# HVSupply.net
KiCad netlist of a schematic drawn in EAGLE
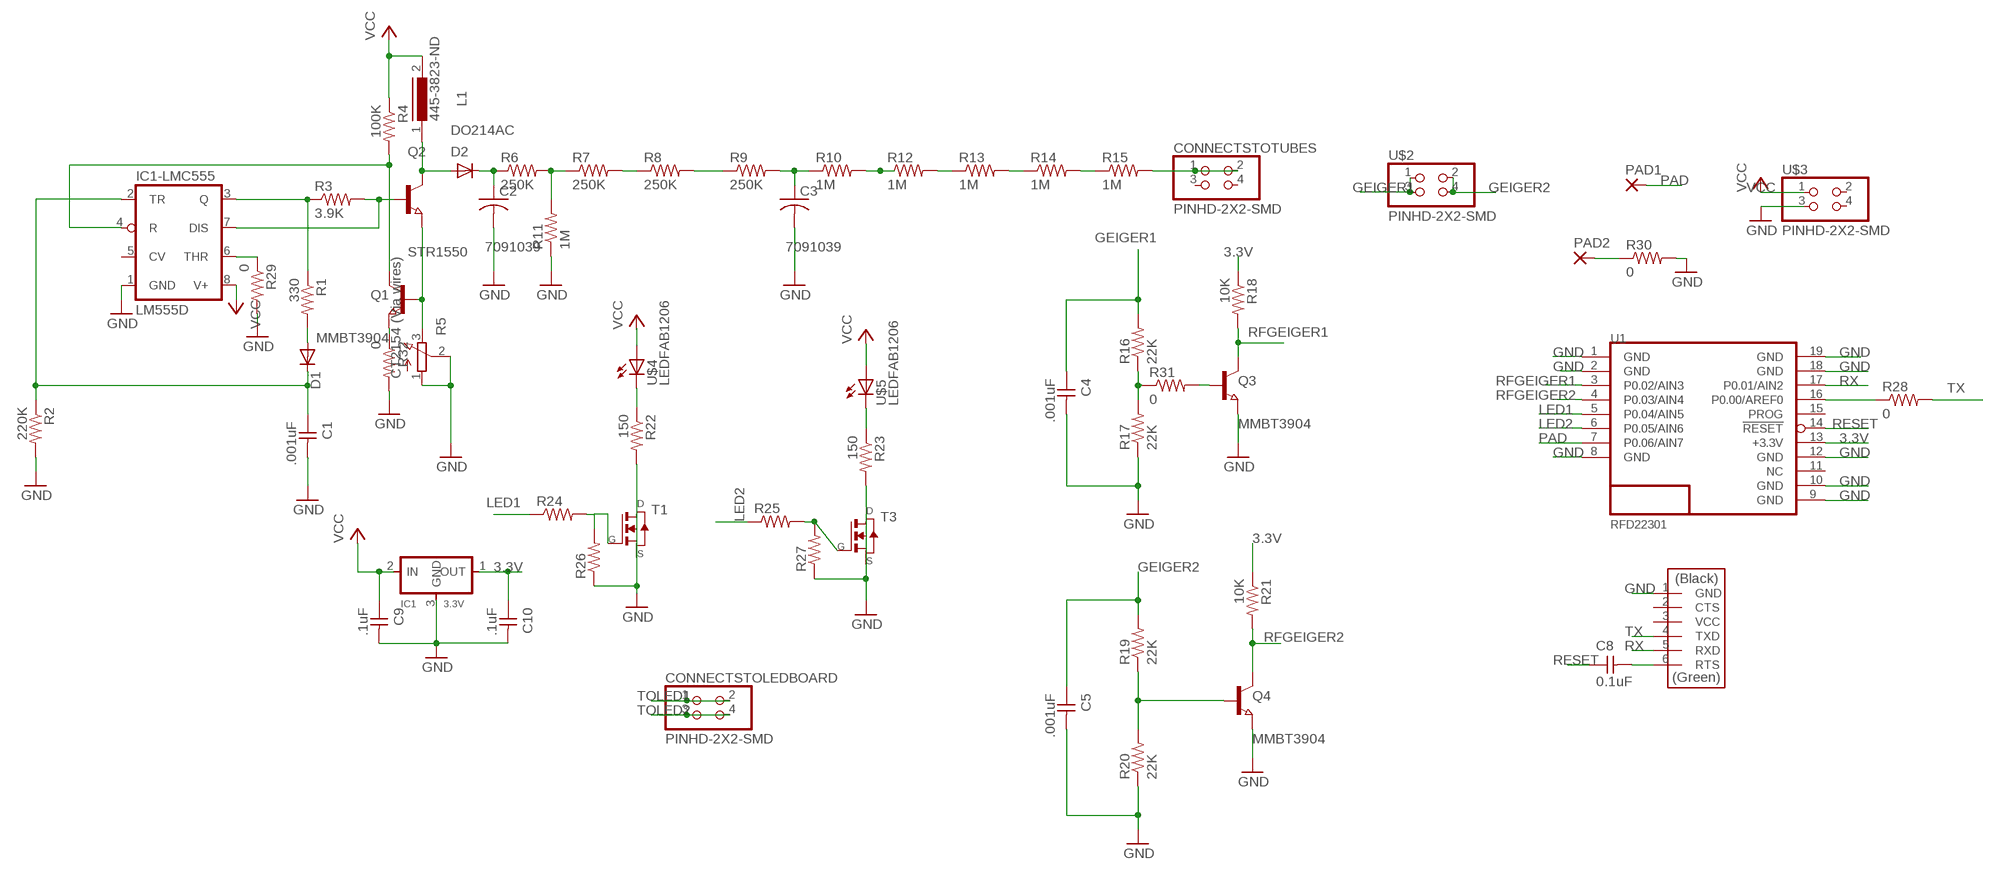
[diagram p0: schematic, sheet 1]

(export (version "E")
  (design (tool "Eeschema 10.0.6"))
  (components
    (comp (ref "C1")
      (value ".001uF")
      (footprint "eagle-import:C1206FAB")
      (libsource (lib "eagle-import") (part "CAP-UNPOLARIZEDFAB"))
    )
    (comp (ref "C2")
      (value "7091039")
      (footprint "eagle-import:C0603K")
      (libsource (lib "eagle-import") (part "C-USC0603K"))
    )
    (comp (ref "C3")
      (value "7091039")
      (footprint "eagle-import:C0603K")
      (libsource (lib "eagle-import") (part "C-USC0603K"))
    )
    (comp (ref "C4")
      (value ".001uF")
      (footprint "eagle-import:C1206FAB")
      (libsource (lib "eagle-import") (part "CAP-UNPOLARIZEDFAB"))
    )
    (comp (ref "C5")
      (value ".001uF")
      (footprint "eagle-import:C1206FAB")
      (libsource (lib "eagle-import") (part "CAP-UNPOLARIZEDFAB"))
    )
    (comp (ref "C8")
      (value "0.1uF")
      (footprint "eagle-import:C1206FAB")
      (libsource (lib "eagle-import") (part "CAP-UNPOLARIZEDFAB"))
    )
    (comp (ref "C9")
      (value ".1uF")
      (footprint "eagle-import:C1206FAB")
      (libsource (lib "eagle-import") (part "CAP-UNPOLARIZEDFAB"))
    )
    (comp (ref "C10")
      (value ".1uF")
      (footprint "eagle-import:C1206FAB")
      (libsource (lib "eagle-import") (part "CAP-UNPOLARIZEDFAB"))
    )
    (comp (ref "CONNECTSTOLEDBOARD")
      (value "PINHD-2X2-SMD")
      (footprint "eagle-import:2X02SMD")
      (libsource (lib "eagle-import") (part "PINHD-2X2-SMD"))
    )
    (comp (ref "CONNECTSTOTUBES")
      (value "PINHD-2X2-SMD")
      (footprint "eagle-import:2X02SMD")
      (libsource (lib "eagle-import") (part "PINHD-2X2-SMD"))
    )
    (comp (ref "D1")
      (value "DIODESOD123")
      (footprint "eagle-import:SOD123")
      (libsource (lib "eagle-import") (part "DIODESOD123"))
    )
    (comp (ref "D2")
      (value "DO214AC")
      (footprint "eagle-import:SMA-DO214AC")
      (libsource (lib "eagle-import") (part "GF1"))
    )
    (comp (ref "IC1")
      (value "3.3V")
      (footprint "eagle-import:SOT23")
      (libsource (lib "eagle-import") (part "REGULATORSOT23"))
    )
    (comp (ref "IC1-LMC555")
      (value "LM555D")
      (footprint "eagle-import:SO08")
      (libsource (lib "eagle-import") (part "555DLM"))
    )
    (comp (ref "L1")
      (value "445-3823-ND")
      (footprint "eagle-import:EMC9714")
      (libsource (lib "eagle-import") (part "EMC9714"))
    )
    (comp (ref "PAD1")
      (value "SMD5")
      (footprint "eagle-import:SMD2,54-5,08")
      (libsource (lib "eagle-import") (part "SMD5"))
    )
    (comp (ref "PAD2")
      (value "SMD5")
      (footprint "eagle-import:SMD2,54-5,08")
      (libsource (lib "eagle-import") (part "SMD5"))
    )
    (comp (ref "Q1")
      (value "MMBT3904")
      (footprint "eagle-import:SOT23")
      (libsource (lib "eagle-import") (part "NPN-TRANSISTOR_SOT23"))
    )
    (comp (ref "Q2")
      (value "STR1550")
      (footprint "eagle-import:SOT23")
      (libsource (lib "eagle-import") (part "NPN-TRANSISTOR_SOT23"))
    )
    (comp (ref "Q3")
      (value "MMBT3904")
      (footprint "eagle-import:SOT23")
      (libsource (lib "eagle-import") (part "NPN-TRANSISTOR_SOT23"))
    )
    (comp (ref "Q4")
      (value "MMBT3904")
      (footprint "eagle-import:SOT23")
      (libsource (lib "eagle-import") (part "NPN-TRANSISTOR_SOT23"))
    )
    (comp (ref "R1")
      (value "330")
      (footprint "eagle-import:R1206FAB")
      (libsource (lib "eagle-import") (part "RES-US1206FAB"))
    )
    (comp (ref "R2")
      (value "220K")
      (footprint "eagle-import:R1206FAB")
      (libsource (lib "eagle-import") (part "RES-US1206FAB"))
    )
    (comp (ref "R3")
      (value "3.9K")
      (footprint "eagle-import:R1206FAB")
      (libsource (lib "eagle-import") (part "RES-US1206FAB"))
    )
    (comp (ref "R4")
      (value "100K")
      (footprint "eagle-import:R1206FAB")
      (libsource (lib "eagle-import") (part "RES-US1206FAB"))
    )
    (comp (ref "R5")
      (value "CT2154 (Via wires)")
      (footprint "eagle-import:3RP_1610N")
      (libsource (lib "eagle-import") (part "3RP/1610N"))
    )
    (comp (ref "R6")
      (value "250K")
      (footprint "eagle-import:R1206FAB")
      (libsource (lib "eagle-import") (part "RES-US1206FAB"))
    )
    (comp (ref "R7")
      (value "250K")
      (footprint "eagle-import:R1206FAB")
      (libsource (lib "eagle-import") (part "RES-US1206FAB"))
    )
    (comp (ref "R8")
      (value "250K")
      (footprint "eagle-import:R1206FAB")
      (libsource (lib "eagle-import") (part "RES-US1206FAB"))
    )
    (comp (ref "R9")
      (value "250K")
      (footprint "eagle-import:R1206FAB")
      (libsource (lib "eagle-import") (part "RES-US1206FAB"))
    )
    (comp (ref "R10")
      (value "1M")
      (footprint "eagle-import:R1206FAB")
      (libsource (lib "eagle-import") (part "RES-US1206FAB"))
    )
    (comp (ref "R11")
      (value "1M")
      (footprint "eagle-import:R1206FAB")
      (libsource (lib "eagle-import") (part "RES-US1206FAB"))
    )
    (comp (ref "R12")
      (value "1M")
      (footprint "eagle-import:R1206FAB")
      (libsource (lib "eagle-import") (part "RES-US1206FAB"))
    )
    (comp (ref "R13")
      (value "1M")
      (footprint "eagle-import:R1206FAB")
      (libsource (lib "eagle-import") (part "RES-US1206FAB"))
    )
    (comp (ref "R14")
      (value "1M")
      (footprint "eagle-import:R1206FAB")
      (libsource (lib "eagle-import") (part "RES-US1206FAB"))
    )
    (comp (ref "R15")
      (value "1M")
      (footprint "eagle-import:R1206FAB")
      (libsource (lib "eagle-import") (part "RES-US1206FAB"))
    )
    (comp (ref "R16")
      (value "22K")
      (footprint "eagle-import:R1206FAB")
      (libsource (lib "eagle-import") (part "RES-US1206FAB"))
    )
    (comp (ref "R17")
      (value "22K")
      (footprint "eagle-import:R1206FAB")
      (libsource (lib "eagle-import") (part "RES-US1206FAB"))
    )
    (comp (ref "R18")
      (value "10K")
      (footprint "eagle-import:R1206FAB")
      (libsource (lib "eagle-import") (part "RES-US1206FAB"))
    )
    (comp (ref "R19")
      (value "22K")
      (footprint "eagle-import:R1206FAB")
      (libsource (lib "eagle-import") (part "RES-US1206FAB"))
    )
    (comp (ref "R20")
      (value "22K")
      (footprint "eagle-import:R1206FAB")
      (libsource (lib "eagle-import") (part "RES-US1206FAB"))
    )
    (comp (ref "R21")
      (value "10K")
      (footprint "eagle-import:R1206FAB")
      (libsource (lib "eagle-import") (part "RES-US1206FAB"))
    )
    (comp (ref "R22")
      (value "150")
      (footprint "eagle-import:R1206FAB")
      (libsource (lib "eagle-import") (part "RES-US1206FAB"))
    )
    (comp (ref "R23")
      (value "150")
      (footprint "eagle-import:R1206FAB")
      (libsource (lib "eagle-import") (part "RES-US1206FAB"))
    )
    (comp (ref "R24")
      (value "RES-US1206FAB")
      (footprint "eagle-import:R1206FAB")
      (libsource (lib "eagle-import") (part "RES-US1206FAB"))
    )
    (comp (ref "R25")
      (value "RES-US1206FAB")
      (footprint "eagle-import:R1206FAB")
      (libsource (lib "eagle-import") (part "RES-US1206FAB"))
    )
    (comp (ref "R26")
      (value "RES-US1206FAB")
      (footprint "eagle-import:R1206FAB")
      (libsource (lib "eagle-import") (part "RES-US1206FAB"))
    )
    (comp (ref "R27")
      (value "RES-US1206FAB")
      (footprint "eagle-import:R1206FAB")
      (libsource (lib "eagle-import") (part "RES-US1206FAB"))
    )
    (comp (ref "R28")
      (value "0")
      (footprint "eagle-import:R1206FAB")
      (libsource (lib "eagle-import") (part "RES-US1206FAB"))
    )
    (comp (ref "R29")
      (value "0")
      (footprint "eagle-import:R1206FAB")
      (libsource (lib "eagle-import") (part "RES-US1206FAB"))
    )
    (comp (ref "R30")
      (value "0")
      (footprint "eagle-import:R1206FAB")
      (libsource (lib "eagle-import") (part "RES-US1206FAB"))
    )
    (comp (ref "R31")
      (value "0")
      (footprint "eagle-import:R1206FAB")
      (libsource (lib "eagle-import") (part "RES-US1206FAB"))
    )
    (comp (ref "R32")
      (value "0")
      (footprint "eagle-import:R1206FAB")
      (libsource (lib "eagle-import") (part "RES-US1206FAB"))
    )
    (comp (ref "T1")
      (value "NMOSFETSOT23")
      (footprint "eagle-import:SOT-23")
      (libsource (lib "eagle-import") (part "NMOSFETSOT23"))
    )
    (comp (ref "T3")
      (value "NMOSFETSOT23")
      (footprint "eagle-import:SOT-23")
      (libsource (lib "eagle-import") (part "NMOSFETSOT23"))
    )
    (comp (ref "U$1")
      (value "FTDI-SMD-HEADER")
      (footprint "eagle-import:1X06SMD")
      (libsource (lib "eagle-import") (part "FTDI-SMD-HEADER"))
    )
    (comp (ref "U$2")
      (value "PINHD-2X2-SMD")
      (footprint "eagle-import:2X02SMD")
      (libsource (lib "eagle-import") (part "PINHD-2X2-SMD"))
    )
    (comp (ref "U$3")
      (value "PINHD-2X2-SMD")
      (footprint "eagle-import:2X02SMD")
      (libsource (lib "eagle-import") (part "PINHD-2X2-SMD"))
    )
    (comp (ref "U$4")
      (value "LEDFAB1206")
      (footprint "eagle-import:LED1206FAB")
      (libsource (lib "eagle-import") (part "LEDFAB1206"))
    )
    (comp (ref "U$5")
      (value "LEDFAB1206")
      (footprint "eagle-import:LED1206FAB")
      (libsource (lib "eagle-import") (part "LEDFAB1206"))
    )
    (comp (ref "U1")
      (value "RFD22301")
      (footprint "eagle-import:RFD22301")
      (libsource (lib "eagle-import") (part "RFD22301"))
    )
  )
  (nets
    (net (code "1") (name "/3.3V") (class "Default")
      (node (ref "C10") (pin "1") (pinfunction "1_1") (pintype "passive"))
      (node (ref "IC1") (pin "1") (pinfunction "OUT_1") (pintype "bidirectional"))
      (node (ref "R18") (pin "1") (pinfunction "1_1") (pintype "passive"))
      (node (ref "R21") (pin "1") (pinfunction "1_1") (pintype "passive"))
      (node (ref "U1") (pin "13") (pinfunction "+3.3V_13") (pintype "bidirectional"))
    )
    (net (code "2") (name "/GEIGER1") (class "Default")
      (node (ref "C4") (pin "1") (pinfunction "1_1") (pintype "passive"))
      (node (ref "R16") (pin "2") (pinfunction "2_2") (pintype "passive"))
      (node (ref "U$2") (pin "1") (pinfunction "1_1") (pintype "passive"))
      (node (ref "U$2") (pin "3") (pinfunction "3_3") (pintype "passive"))
    )
    (net (code "3") (name "/GEIGER2") (class "Default")
      (node (ref "C5") (pin "1") (pinfunction "1_1") (pintype "passive"))
      (node (ref "R19") (pin "2") (pinfunction "2_2") (pintype "passive"))
      (node (ref "U$2") (pin "2") (pinfunction "2_2") (pintype "passive"))
      (node (ref "U$2") (pin "4") (pinfunction "4_4") (pintype "passive"))
    )
    (net (code "4") (name "/LED1") (class "Default")
      (node (ref "R24") (pin "1") (pinfunction "1_1") (pintype "passive"))
      (node (ref "U1") (pin "5") (pinfunction "P0.04/AIN5_5") (pintype "bidirectional"))
    )
    (net (code "5") (name "/LED2") (class "Default")
      (node (ref "R25") (pin "1") (pinfunction "1_1") (pintype "passive"))
      (node (ref "U1") (pin "6") (pinfunction "P0.05/AIN6_6") (pintype "bidirectional"))
    )
    (net (code "6") (name "/PAD") (class "Default")
      (node (ref "PAD1") (pin "1") (pinfunction "P_1") (pintype "passive"))
      (node (ref "U1") (pin "7") (pinfunction "P0.06/AIN7_7") (pintype "bidirectional"))
    )
    (net (code "7") (name "/RESET") (class "Default")
      (node (ref "C8") (pin "1") (pinfunction "1_1") (pintype "passive"))
      (node (ref "U1") (pin "14") (pinfunction "~{RESET}_14") (pintype "bidirectional"))
    )
    (net (code "8") (name "/RFGEIGER1") (class "Default")
      (node (ref "Q3") (pin "3") (pinfunction "C_3") (pintype "passive"))
      (node (ref "R18") (pin "2") (pinfunction "2_2") (pintype "passive"))
      (node (ref "U1") (pin "3") (pinfunction "P0.02/AIN3_3") (pintype "bidirectional"))
    )
    (net (code "9") (name "/RFGEIGER2") (class "Default")
      (node (ref "Q4") (pin "3") (pinfunction "C_3") (pintype "passive"))
      (node (ref "R21") (pin "2") (pinfunction "2_2") (pintype "passive"))
      (node (ref "U1") (pin "4") (pinfunction "P0.03/AIN4_4") (pintype "bidirectional"))
    )
    (net (code "10") (name "/RX") (class "Default")
      (node (ref "U$1") (pin "5") (pinfunction "RXD_5") (pintype "bidirectional"))
      (node (ref "U1") (pin "17") (pinfunction "P0.01/AIN2_17") (pintype "bidirectional"))
    )
    (net (code "11") (name "/TOLED1") (class "Default")
      (node (ref "CONNECTSTOLEDBOARD") (pin "1") (pinfunction "1_1") (pintype "passive"))
      (node (ref "CONNECTSTOLEDBOARD") (pin "2") (pinfunction "2_2") (pintype "passive"))
      (node (ref "R22") (pin "2") (pinfunction "2_2") (pintype "passive"))
      (node (ref "T1") (pin "2") (pinfunction "S_2") (pintype "passive"))
    )
    (net (code "12") (name "/TOLED2") (class "Default")
      (node (ref "CONNECTSTOLEDBOARD") (pin "3") (pinfunction "3_3") (pintype "passive"))
      (node (ref "CONNECTSTOLEDBOARD") (pin "4") (pinfunction "4_4") (pintype "passive"))
      (node (ref "R23") (pin "2") (pinfunction "2_2") (pintype "passive"))
      (node (ref "T3") (pin "2") (pinfunction "S_2") (pintype "passive"))
    )
    (net (code "13") (name "/TX") (class "Default")
      (node (ref "R28") (pin "2") (pinfunction "2_2") (pintype "passive"))
      (node (ref "U$1") (pin "4") (pinfunction "TXD_4") (pintype "bidirectional"))
    )
    (net (code "14") (name "GND") (class "Default")
      (node (ref "C1") (pin "2") (pinfunction "2_2") (pintype "passive"))
      (node (ref "C10") (pin "2") (pinfunction "2_2") (pintype "passive"))
      (node (ref "C2") (pin "2") (pinfunction "2_2") (pintype "passive"))
      (node (ref "C3") (pin "2") (pinfunction "2_2") (pintype "passive"))
      (node (ref "C4") (pin "2") (pinfunction "2_2") (pintype "passive"))
      (node (ref "C5") (pin "2") (pinfunction "2_2") (pintype "passive"))
      (node (ref "C9") (pin "2") (pinfunction "2_2") (pintype "passive"))
      (node (ref "IC1") (pin "3") (pinfunction "GND_3") (pintype "bidirectional"))
      (node (ref "IC1-LMC555") (pin "1") (pinfunction "GND_1") (pintype "power_in"))
      (node (ref "Q3") (pin "2") (pinfunction "E_2") (pintype "passive"))
      (node (ref "Q4") (pin "2") (pinfunction "E_2") (pintype "passive"))
      (node (ref "R11") (pin "1") (pinfunction "1_1") (pintype "passive"))
      (node (ref "R17") (pin "1") (pinfunction "1_1") (pintype "passive"))
      (node (ref "R2") (pin "2") (pinfunction "2_2") (pintype "passive"))
      (node (ref "R20") (pin "1") (pinfunction "1_1") (pintype "passive"))
      (node (ref "R26") (pin "1") (pinfunction "1_1") (pintype "passive"))
      (node (ref "R27") (pin "1") (pinfunction "1_1") (pintype "passive"))
      (node (ref "R29") (pin "2") (pinfunction "2_2") (pintype "passive"))
      (node (ref "R30") (pin "2") (pinfunction "2_2") (pintype "passive"))
      (node (ref "R32") (pin "2") (pinfunction "2_2") (pintype "passive"))
      (node (ref "R5") (pin "1") (pinfunction "A_1") (pintype "passive"))
      (node (ref "R5") (pin "2") (pinfunction "S_2") (pintype "passive"))
      (node (ref "T1") (pin "1") (pinfunction "D_1") (pintype "passive"))
      (node (ref "T3") (pin "1") (pinfunction "D_1") (pintype "passive"))
      (node (ref "U$1") (pin "1") (pinfunction "GND_1") (pintype "bidirectional"))
      (node (ref "U$3") (pin "3") (pinfunction "3_3") (pintype "passive"))
      (node (ref "U1") (pin "1") (pinfunction "GND_1") (pintype "bidirectional"))
      (node (ref "U1") (pin "10") (pinfunction "GND_10") (pintype "bidirectional"))
      (node (ref "U1") (pin "12") (pinfunction "GND_12") (pintype "bidirectional"))
      (node (ref "U1") (pin "18") (pinfunction "GND_18") (pintype "bidirectional"))
      (node (ref "U1") (pin "19") (pinfunction "GND_19") (pintype "bidirectional"))
      (node (ref "U1") (pin "2") (pinfunction "GND_2") (pintype "bidirectional"))
      (node (ref "U1") (pin "8") (pinfunction "GND_8") (pintype "bidirectional"))
      (node (ref "U1") (pin "9") (pinfunction "GND_9") (pintype "bidirectional"))
    )
    (net (code "15") (name "Net-(C3-Pad1)") (class "Default")
      (node (ref "C3") (pin "1") (pinfunction "1_1") (pintype "passive"))
      (node (ref "R10") (pin "1") (pinfunction "1_1") (pintype "passive"))
      (node (ref "R9") (pin "2") (pinfunction "2_2") (pintype "passive"))
    )
    (net (code "16") (name "Net-(CONNECTSTOTUBES-Pad1)") (class "Default")
      (node (ref "CONNECTSTOTUBES") (pin "1") (pinfunction "1_1") (pintype "passive"))
      (node (ref "CONNECTSTOTUBES") (pin "2") (pinfunction "2_2") (pintype "passive"))
      (node (ref "R15") (pin "2") (pinfunction "2_2") (pintype "passive"))
    )
    (net (code "17") (name "Net-(D1-A)") (class "Default")
      (node (ref "D1") (pin "ANODE") (pinfunction "A_ANODE") (pintype "passive"))
      (node (ref "R1") (pin "2") (pinfunction "2_2") (pintype "passive"))
    )
    (net (code "18") (name "Net-(D1-C)") (class "Default")
      (node (ref "C1") (pin "1") (pinfunction "1_1") (pintype "passive"))
      (node (ref "D1") (pin "CATHODE") (pinfunction "C_CATHODE") (pintype "passive"))
      (node (ref "IC1-LMC555") (pin "2") (pinfunction "TR_2") (pintype "input"))
      (node (ref "R2") (pin "1") (pinfunction "1_1") (pintype "passive"))
    )
    (net (code "19") (name "Net-(D2-C)") (class "Default")
      (node (ref "C2") (pin "1") (pinfunction "1_1") (pintype "passive"))
      (node (ref "D2") (pin "K") (pinfunction "C_K") (pintype "passive"))
      (node (ref "R6") (pin "1") (pinfunction "1_1") (pintype "passive"))
    )
    (net (code "20") (name "Net-(IC1-LMC555-DIS)") (class "Default")
      (node (ref "IC1-LMC555") (pin "7") (pinfunction "DIS_7") (pintype "input"))
      (node (ref "Q2") (pin "1") (pinfunction "B_1") (pintype "passive"))
      (node (ref "R3") (pin "2") (pinfunction "2_2") (pintype "passive"))
    )
    (net (code "21") (name "Net-(IC1-LMC555-Q)") (class "Default")
      (node (ref "IC1-LMC555") (pin "3") (pinfunction "Q_3") (pintype "output"))
      (node (ref "R1") (pin "1") (pinfunction "1_1") (pintype "passive"))
      (node (ref "R3") (pin "1") (pinfunction "1_1") (pintype "passive"))
    )
    (net (code "22") (name "Net-(IC1-LMC555-R)") (class "Default")
      (node (ref "IC1-LMC555") (pin "4") (pinfunction "R_4") (pintype "input"))
      (node (ref "Q1") (pin "3") (pinfunction "C_3") (pintype "passive"))
      (node (ref "R4") (pin "2") (pinfunction "2_2") (pintype "passive"))
    )
    (net (code "23") (name "Net-(IC1-LMC555-THR)") (class "Default")
      (node (ref "IC1-LMC555") (pin "6") (pinfunction "THR_6") (pintype "input"))
      (node (ref "R29") (pin "1") (pinfunction "1_1") (pintype "passive"))
    )
    (net (code "24") (name "Net-(PAD2-P)") (class "Default")
      (node (ref "PAD2") (pin "1") (pinfunction "P_1") (pintype "passive"))
      (node (ref "R30") (pin "1") (pinfunction "1_1") (pintype "passive"))
    )
    (net (code "25") (name "Net-(Q1-B)") (class "Default")
      (node (ref "Q1") (pin "1") (pinfunction "B_1") (pintype "passive"))
      (node (ref "Q2") (pin "2") (pinfunction "E_2") (pintype "passive"))
      (node (ref "R5") (pin "3") (pinfunction "E_3") (pintype "passive"))
    )
    (net (code "26") (name "Net-(Q1-E)") (class "Default")
      (node (ref "Q1") (pin "2") (pinfunction "E_2") (pintype "passive"))
      (node (ref "R32") (pin "1") (pinfunction "1_1") (pintype "passive"))
    )
    (net (code "27") (name "Net-(Q2-C)") (class "Default")
      (node (ref "D2") (pin "A") (pinfunction "A_A") (pintype "passive"))
      (node (ref "L1") (pin "1") (pinfunction "1_1") (pintype "passive"))
      (node (ref "Q2") (pin "3") (pinfunction "C_3") (pintype "passive"))
    )
    (net (code "28") (name "Net-(Q3-B)") (class "Default")
      (node (ref "Q3") (pin "1") (pinfunction "B_1") (pintype "passive"))
      (node (ref "R31") (pin "2") (pinfunction "2_2") (pintype "passive"))
    )
    (net (code "29") (name "Net-(Q4-B)") (class "Default")
      (node (ref "Q4") (pin "1") (pinfunction "B_1") (pintype "passive"))
      (node (ref "R19") (pin "1") (pinfunction "1_1") (pintype "passive"))
      (node (ref "R20") (pin "2") (pinfunction "2_2") (pintype "passive"))
    )
    (net (code "30") (name "Net-(R7-Pad2)") (class "Default")
      (node (ref "R7") (pin "2") (pinfunction "2_2") (pintype "passive"))
      (node (ref "R8") (pin "1") (pinfunction "1_1") (pintype "passive"))
    )
    (net (code "31") (name "Net-(R8-Pad2)") (class "Default")
      (node (ref "R8") (pin "2") (pinfunction "2_2") (pintype "passive"))
      (node (ref "R9") (pin "1") (pinfunction "1_1") (pintype "passive"))
    )
    (net (code "32") (name "Net-(R10-Pad2)") (class "Default")
      (node (ref "R10") (pin "2") (pinfunction "2_2") (pintype "passive"))
      (node (ref "R12") (pin "1") (pinfunction "1_1") (pintype "passive"))
    )
    (net (code "33") (name "Net-(R11-Pad2)") (class "Default")
      (node (ref "R11") (pin "2") (pinfunction "2_2") (pintype "passive"))
      (node (ref "R6") (pin "2") (pinfunction "2_2") (pintype "passive"))
      (node (ref "R7") (pin "1") (pinfunction "1_1") (pintype "passive"))
    )
    (net (code "34") (name "Net-(R12-Pad2)") (class "Default")
      (node (ref "R12") (pin "2") (pinfunction "2_2") (pintype "passive"))
      (node (ref "R13") (pin "1") (pinfunction "1_1") (pintype "passive"))
    )
    (net (code "35") (name "Net-(R13-Pad2)") (class "Default")
      (node (ref "R13") (pin "2") (pinfunction "2_2") (pintype "passive"))
      (node (ref "R14") (pin "1") (pinfunction "1_1") (pintype "passive"))
    )
    (net (code "36") (name "Net-(R14-Pad2)") (class "Default")
      (node (ref "R14") (pin "2") (pinfunction "2_2") (pintype "passive"))
      (node (ref "R15") (pin "1") (pinfunction "1_1") (pintype "passive"))
    )
    (net (code "37") (name "Net-(R16-Pad1)") (class "Default")
      (node (ref "R16") (pin "1") (pinfunction "1_1") (pintype "passive"))
      (node (ref "R17") (pin "2") (pinfunction "2_2") (pintype "passive"))
      (node (ref "R31") (pin "1") (pinfunction "1_1") (pintype "passive"))
    )
    (net (code "38") (name "Net-(T1-G)") (class "Default")
      (node (ref "R24") (pin "2") (pinfunction "2_2") (pintype "passive"))
      (node (ref "R26") (pin "2") (pinfunction "2_2") (pintype "passive"))
      (node (ref "T1") (pin "3") (pinfunction "G_3") (pintype "passive"))
    )
    (net (code "39") (name "Net-(T3-G)") (class "Default")
      (node (ref "R25") (pin "2") (pinfunction "2_2") (pintype "passive"))
      (node (ref "R27") (pin "2") (pinfunction "2_2") (pintype "passive"))
      (node (ref "T3") (pin "3") (pinfunction "G_3") (pintype "passive"))
    )
    (net (code "40") (name "Net-(U$1-RTS)") (class "Default")
      (node (ref "C8") (pin "2") (pinfunction "2_2") (pintype "passive"))
      (node (ref "U$1") (pin "6") (pinfunction "RTS_6") (pintype "bidirectional"))
    )
    (net (code "41") (name "Net-(U$4-C)") (class "Default")
      (node (ref "R22") (pin "1") (pinfunction "1_1") (pintype "passive"))
      (node (ref "U$4") (pin "2") (pinfunction "C_2") (pintype "passive"))
    )
    (net (code "42") (name "Net-(U$5-C)") (class "Default")
      (node (ref "R23") (pin "1") (pinfunction "1_1") (pintype "passive"))
      (node (ref "U$5") (pin "2") (pinfunction "C_2") (pintype "passive"))
    )
    (net (code "43") (name "Net-(U1-P0.00{slash}AREF0)") (class "Default")
      (node (ref "R28") (pin "1") (pinfunction "1_1") (pintype "passive"))
      (node (ref "U1") (pin "16") (pinfunction "P0.00/AREF0_16") (pintype "bidirectional"))
    )
    (net (code "44") (name "VCC") (class "Default")
      (node (ref "C9") (pin "1") (pinfunction "1_1") (pintype "passive"))
      (node (ref "IC1") (pin "2") (pinfunction "IN_2") (pintype "bidirectional"))
      (node (ref "IC1-LMC555") (pin "8") (pinfunction "V+_8") (pintype "power_in"))
      (node (ref "L1") (pin "2") (pinfunction "2_2") (pintype "passive"))
      (node (ref "R4") (pin "1") (pinfunction "1_1") (pintype "passive"))
      (node (ref "U$3") (pin "1") (pinfunction "1_1") (pintype "passive"))
      (node (ref "U$5") (pin "1") (pinfunction "A_1") (pintype "passive"))
    )
    (net (code "45") (name "unconnected-(CONNECTSTOTUBES-Pad3)") (class "Default")
      (node (ref "CONNECTSTOTUBES") (pin "3") (pinfunction "3_3") (pintype "passive"))
    )
    (net (code "46") (name "unconnected-(CONNECTSTOTUBES-Pad4)") (class "Default")
      (node (ref "CONNECTSTOTUBES") (pin "4") (pinfunction "4_4") (pintype "passive"))
    )
    (net (code "47") (name "unconnected-(IC1-LMC555-CV-Pad5)") (class "Default")
      (node (ref "IC1-LMC555") (pin "5") (pinfunction "CV_5") (pintype "input"))
    )
    (net (code "48") (name "unconnected-(U$1-CTS-Pad2)") (class "Default")
      (node (ref "U$1") (pin "2") (pinfunction "CTS_2") (pintype "bidirectional"))
    )
    (net (code "49") (name "unconnected-(U$1-VCC-Pad3)") (class "Default")
      (node (ref "U$1") (pin "3") (pinfunction "VCC_3") (pintype "bidirectional"))
    )
    (net (code "50") (name "unconnected-(U$3-Pad2)") (class "Default")
      (node (ref "U$3") (pin "2") (pinfunction "2_2") (pintype "passive"))
    )
    (net (code "51") (name "unconnected-(U$3-Pad4)") (class "Default")
      (node (ref "U$3") (pin "4") (pinfunction "4_4") (pintype "passive"))
    )
    (net (code "52") (name "unconnected-(U$4-A-Pad1)") (class "Default")
      (node (ref "U$4") (pin "1") (pinfunction "A_1") (pintype "passive"))
    )
    (net (code "53") (name "unconnected-(U1-NC-Pad11)") (class "Default")
      (node (ref "U1") (pin "11") (pinfunction "NC_11") (pintype "no_connect"))
    )
    (net (code "54") (name "unconnected-(U1-PROG-Pad15)") (class "Default")
      (node (ref "U1") (pin "15") (pinfunction "PROG_15") (pintype "bidirectional"))
    )
  )
)
